# esp32v4.net
KiCad netlist of a schematic drawn in Altium Designer
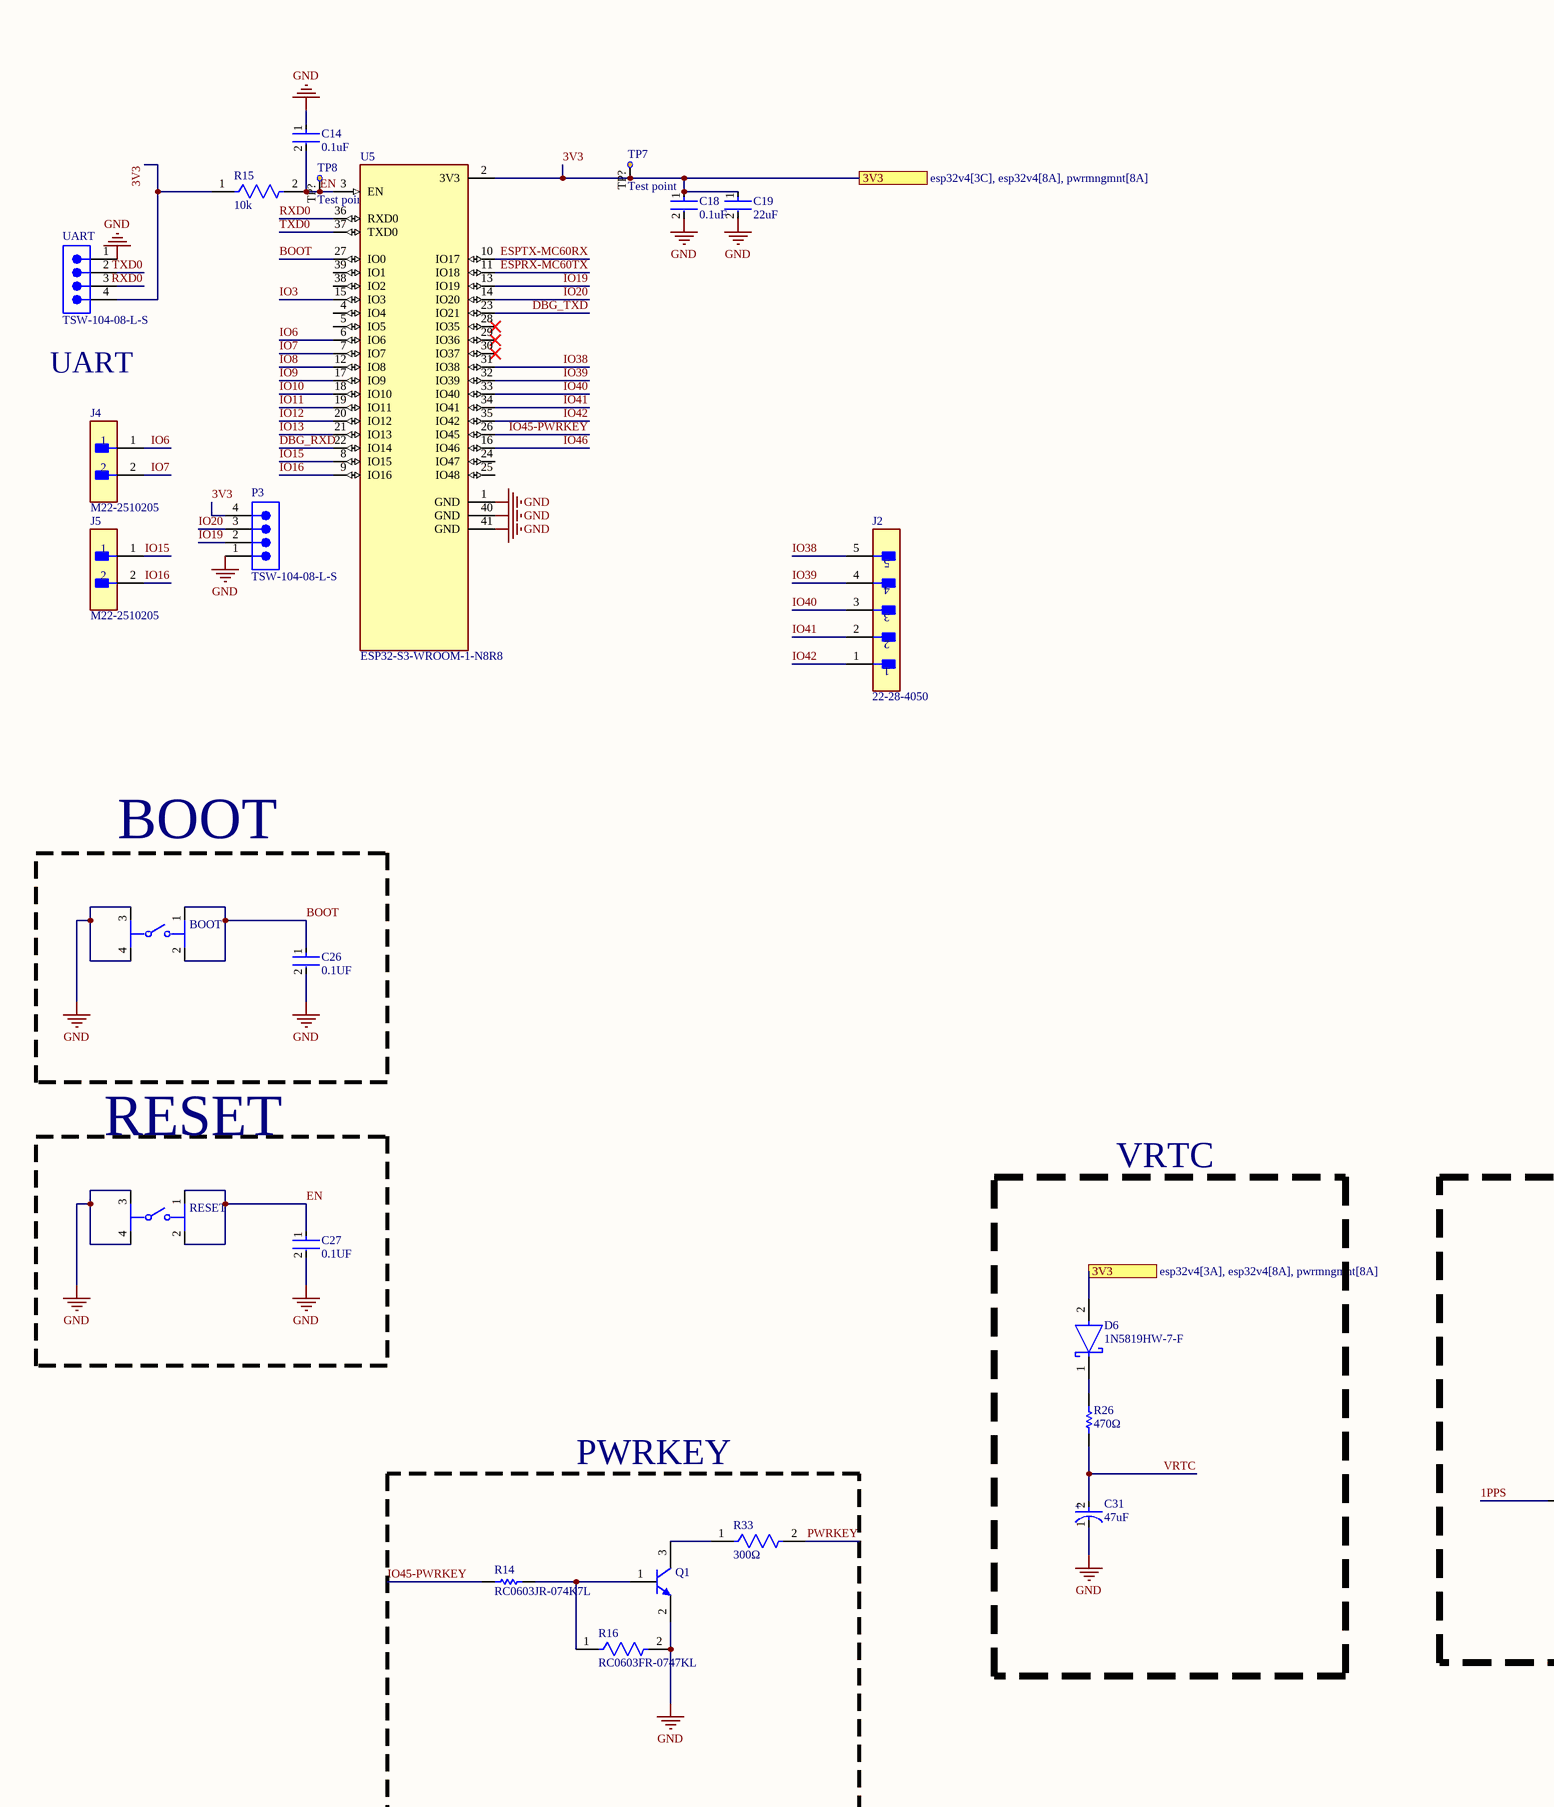
[diagram p0: esp32v4.SchDoc, left]
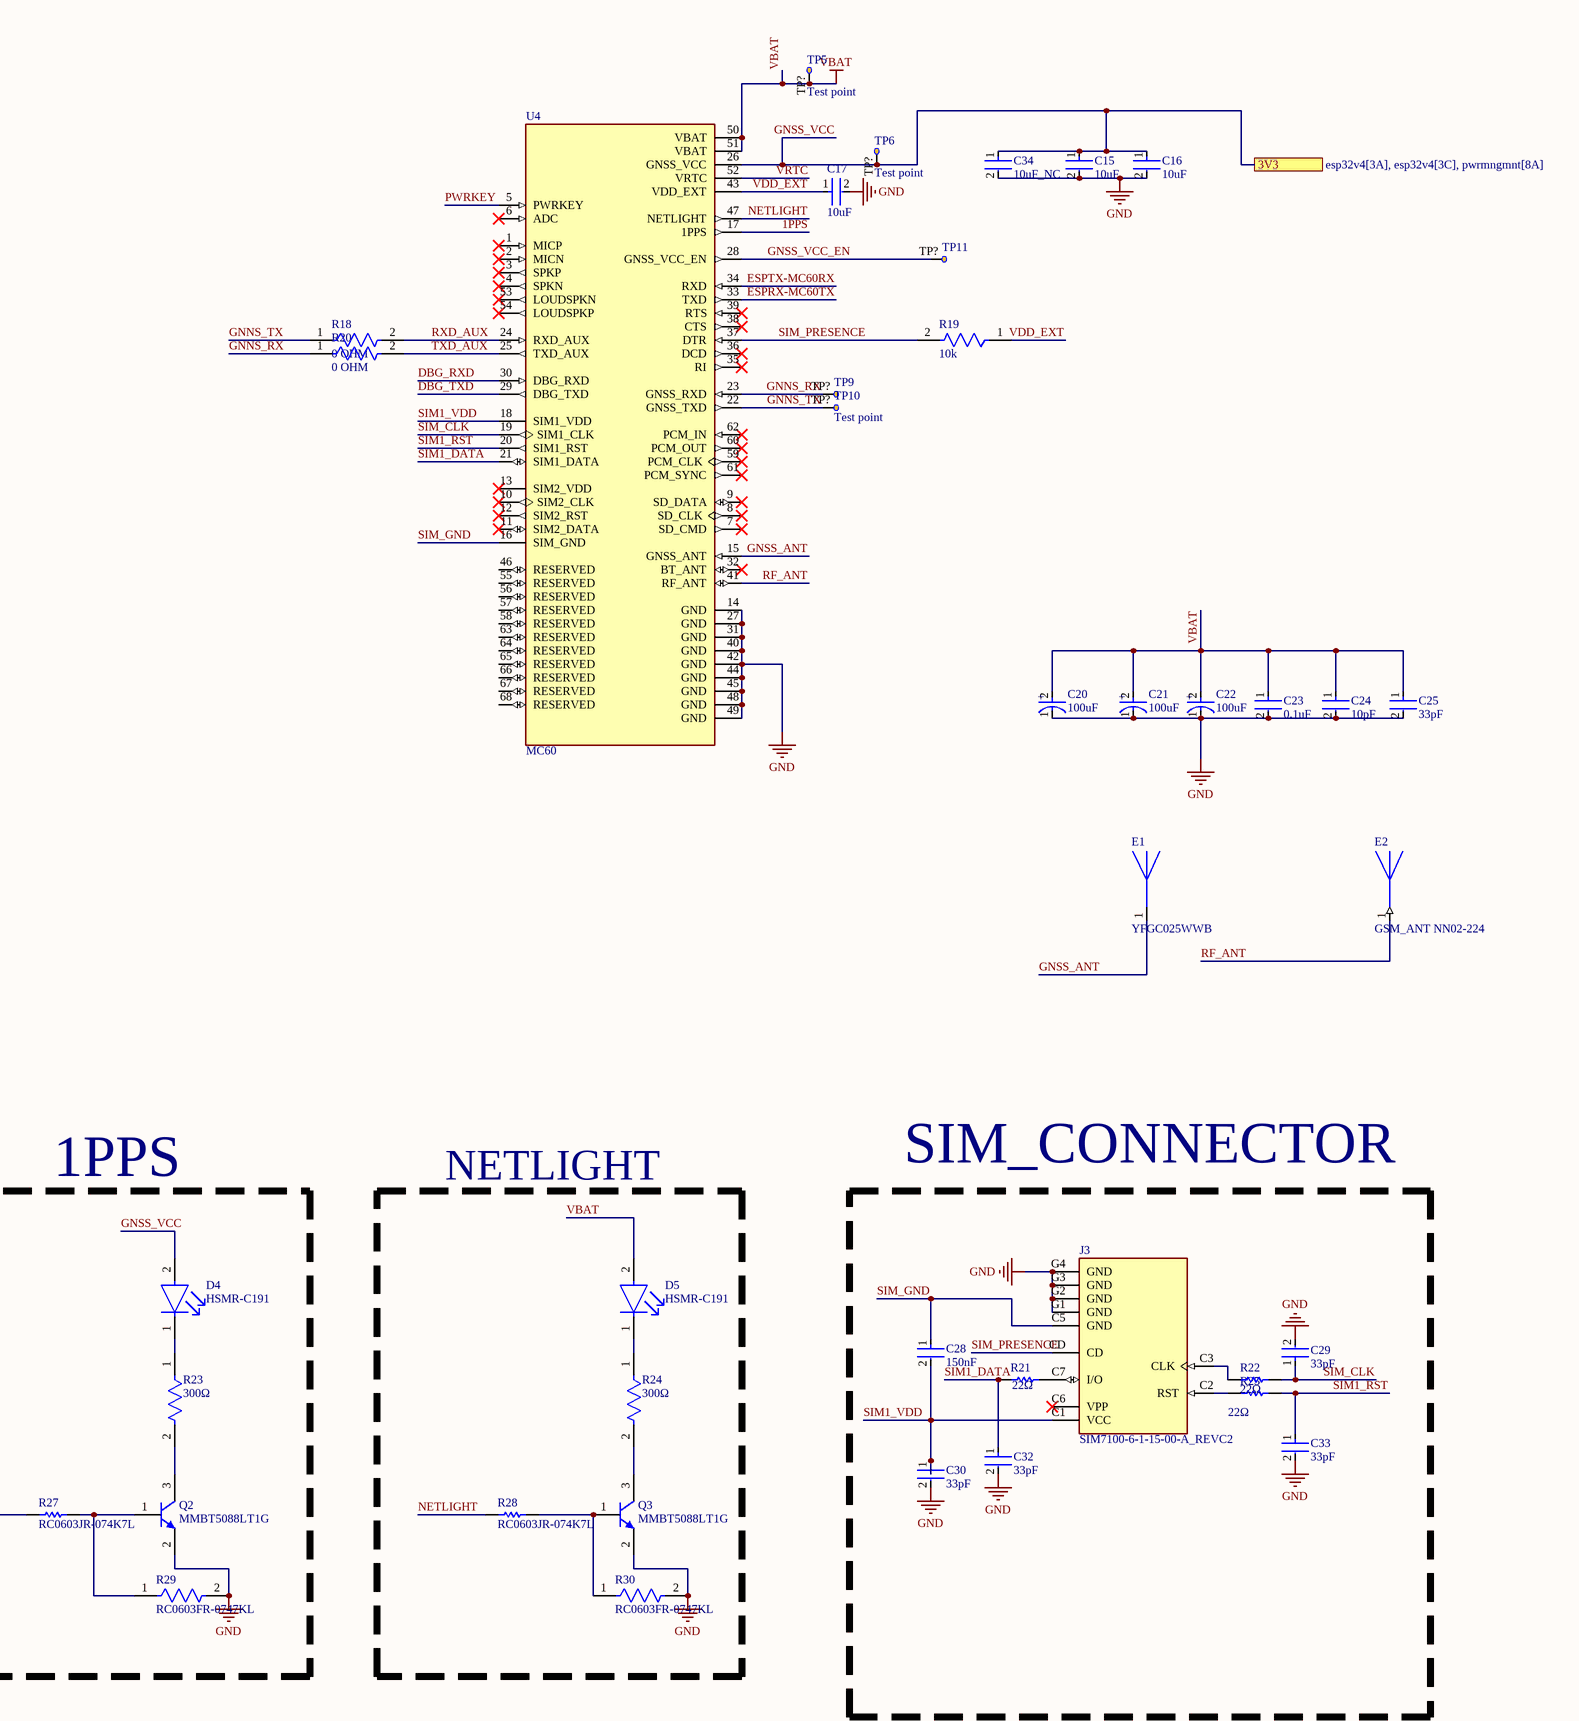
[diagram p1: esp32v4.SchDoc, right]

(export (version "E")
  (design (tool "Eeschema 10.0.6"))
  (components
    (comp (ref "BOOT")
      (value "PTS810SJM250SMTRLFS")
      (footprint "FP-PTS810SJM250SMTRLFS-MFG")
      (description "SWITCH TACTILE SPST-NO 0.05A 16V")
      (libsource (lib "Altium Content Vault") (part "1adf0dd01260c80cf25a44bfd6b99ba"))
    )
    (comp (ref "C14")
      (value "0.1uF")
      (footprint "FP-CC0805-0_85-MFG")
      (description "CAP CER 0.1UF 50V X7R 0805")
      (fields (field (name "TOLERANCE") "0.1") (field (name "MANUFACTURER PART NUMBER") "CC0805KRX7R9BB104"))
      (libsource (lib "Altium Content Vault") (part "11868f565c42a9108669ba33697ecf6"))
    )
    (comp (ref "C15")
      (value "10uF")
      (footprint "FP-C0805C106K4PACTU-MFG")
      (description "CAP CER 10UF 16V X5R 0805")
      (fields (field (name "TOLERANCE") "10%") (field (name "VOLTAGE") "16V"))
      (libsource (lib "Altium Content Vault") (part "e9c51b7dd13d4faca003ae77663ab08"))
    )
    (comp (ref "C16")
      (value "10uF")
      (footprint "FP-CC0805-0_85-MFG")
      (description "CAP CER 0.1UF 25V X7R 0805")
      (fields (field (name "MANUFACTURER PART NUMBER") "CC0805KRX7R8BB104") (field (name "TOLERANCE") "0.1"))
      (libsource (lib "Altium Content Vault") (part "11868f565c42a9108669ba33697ecf6"))
    )
    (comp (ref "C17")
      (value "10uF")
      (footprint "FP-C0805C106K4PACTU-MFG")
      (description "CAP CER 10UF 16V X5R 0805")
      (fields (field (name "TOLERANCE") "10%") (field (name "VOLTAGE") "16V"))
      (libsource (lib "Altium Content Vault") (part "e9c51b7dd13d4faca003ae77663ab08"))
    )
    (comp (ref "C18")
      (value "0.1uF")
      (footprint "FP-CC0805-0_85-MFG")
      (description "CAP CER 0.1UF 25V X7R 0805")
      (fields (field (name "MANUFACTURER PART NUMBER") "CC0805KRX7R8BB104") (field (name "TOLERANCE") "0.1"))
      (libsource (lib "Altium Content Vault") (part "11868f565c42a9108669ba33697ecf6"))
    )
    (comp (ref "C19")
      (value "22uF")
      (footprint "FP-GRM21B-0_15-MFG")
      (description "Chip Multilayer Ceramic Capacitors for General Purpose, 0805, 22uF, X5R, 15%, 20%, 6.3V")
      (fields (field (name "VOLTAGE") "6.3V") (field (name "TOLERANCE") "20%"))
      (libsource (lib "Altium Content Vault") (part "b4654b650e69147ec39a6b967a45e02"))
    )
    (comp (ref "C20")
      (value "100uF")
      (footprint "FP-SC-MFG")
      (description "CAP ALUM 100UF 20% 10V SMD")
      (fields (field (name "TOLERANCE") "20%"))
      (libsource (lib "Altium Content Vault") (part "a00bbbee19879c290e62620ae7e47b1"))
    )
    (comp (ref "C21")
      (value "100uF")
      (footprint "FP-SC-MFG")
      (description "CAP ALUM 100UF 20% 10V SMD")
      (fields (field (name "TOLERANCE") "20%"))
      (libsource (lib "Altium Content Vault") (part "a00bbbee19879c290e62620ae7e47b1"))
    )
    (comp (ref "C22")
      (value "100uF")
      (footprint "FP-SC-MFG")
      (description "CAP ALUM 100UF 20% 10V SMD")
      (fields (field (name "TOLERANCE") "20%"))
      (libsource (lib "Altium Content Vault") (part "a00bbbee19879c290e62620ae7e47b1"))
    )
    (comp (ref "C23")
      (value "0.1uF")
      (footprint "FP-CC0805-0_85-MFG")
      (description "CAP CER 0.1UF 25V X7R 0805")
      (fields (field (name "MANUFACTURER PART NUMBER") "CC0805KRX7R8BB104") (field (name "TOLERANCE") "0.1"))
      (libsource (lib "Altium Content Vault") (part "11868f565c42a9108669ba33697ecf6"))
    )
    (comp (ref "C24")
      (value "10pF")
      (footprint "FP-C0805C-DN-MFG")
      (description "Cap Ceramic 10pF 100V C0G 5% SMD 0805 125C Plastic T/R")
      (fields
        (field (name "MANUFACTURER PART NUMBER") "C0805C100J1GACTU")
        (field (name "OCTOPART") "https://octopart.com/c0805c100j1gactu-kemet-127179")
      )
      (libsource (lib "Altium Content Vault") (part "b4654b650e69147ec39a6b967a45e02"))
    )
    (comp (ref "C25")
      (value "33pF")
      (footprint "FP-C0603C-CF-MFG")
      (description "Capacitor; Ceramic; Cap; 33.0pF; Tol 5%; SMT; Vol-Rtg 50V; C0G; Tape and Reel")
      (fields (field (name "MANUFACTURER PART NUMBER") "C0603C330J5GACTU") (field (name "TOLERANCE") "0.05"))
      (libsource (lib "Altium Content Vault") (part "b4654b650e69147ec39a6b967a45e02"))
    )
    (comp (ref "C26")
      (value "0.1UF")
      (footprint "FP-CC0805-0_85-MFG")
      (description "CAP CER 0.1UF 50V X7R 0805")
      (fields (field (name "TOLERANCE") "0.1") (field (name "MANUFACTURER PART NUMBER") "CC0805KRX7R9BB104"))
      (libsource (lib "Altium Content Vault") (part "11868f565c42a9108669ba33697ecf6"))
    )
    (comp (ref "C27")
      (value "0.1UF")
      (footprint "FP-CC0805-0_85-MFG")
      (description "CAP CER 0.1UF 50V X7R 0805")
      (fields (field (name "TOLERANCE") "0.1") (field (name "MANUFACTURER PART NUMBER") "CC0805KRX7R9BB104"))
      (libsource (lib "Altium Content Vault") (part "11868f565c42a9108669ba33697ecf6"))
    )
    (comp (ref "C28")
      (value "150nF")
      (footprint "FP-CL21-IPC_C")
      (description "CL21 Series 0805 150nF 16V ±10% Tolerance X7R Multilayer Ceramic Chip Capacitor")
      (fields (field (name "TOLERANCE") "10%"))
      (libsource (lib "Altium Content Vault") (part "b4654b650e69147ec39a6b967a45e02"))
    )
    (comp (ref "C29")
      (value "33pF")
      (footprint "FP-0603-L_1_6_0_15-W_0_81-IPC_C")
      (description "General Purpose Ceramic Capacitor, 0603, 33pF, 5%, NP0, 30ppm/°C, 50V")
      (fields (field (name "TOLERANCE") "5%") (field (name "VOLTAGE") "50V"))
      (libsource (lib "Altium Content Vault") (part "02cd4be3c70576c341d710602a673aa"))
    )
    (comp (ref "C30")
      (value "33pF")
      (footprint "FP-0603-L_1_6_0_15-W_0_81-IPC_C")
      (description "General Purpose Ceramic Capacitor, 0603, 33pF, 5%, NP0, 30ppm/°C, 50V")
      (fields (field (name "TOLERANCE") "5%") (field (name "VOLTAGE") "50V"))
      (libsource (lib "Altium Content Vault") (part "02cd4be3c70576c341d710602a673aa"))
    )
    (comp (ref "C31")
      (value "47uF")
      (footprint "FP-OS-CON-SMT-C6-MFG")
      (description "Conductive Polymer Aluminum Solid Capacitors (OS-CON) 47uF ±20% 10V")
      (fields (field (name "TOLERANCE") "20%") (field (name "VOLTAGE") "10V"))
      (libsource (lib "Altium Content Vault") (part "a00bbbee19879c290e62620ae7e47b1"))
    )
    (comp (ref "C32")
      (value "33pF")
      (footprint "FP-0603-L_1_6_0_15-W_0_81-IPC_C")
      (description "General Purpose Ceramic Capacitor, 0603, 33pF, 5%, NP0, 30ppm/°C, 50V")
      (fields (field (name "TOLERANCE") "5%") (field (name "VOLTAGE") "50V"))
      (libsource (lib "Altium Content Vault") (part "02cd4be3c70576c341d710602a673aa"))
    )
    (comp (ref "C33")
      (value "33pF")
      (footprint "FP-0603-L_1_6_0_15-W_0_81-IPC_C")
      (description "General Purpose Ceramic Capacitor, 0603, 33pF, 5%, NP0, 30ppm/°C, 50V")
      (fields (field (name "TOLERANCE") "5%") (field (name "VOLTAGE") "50V"))
      (libsource (lib "Altium Content Vault") (part "02cd4be3c70576c341d710602a673aa"))
    )
    (comp (ref "C34")
      (value "10uF_NC")
      (footprint "FP-C0805C106K4PACTU-MFG")
      (description "CAP CER 10UF 16V X5R 0805")
      (fields (field (name "TOLERANCE") "10%") (field (name "VOLTAGE") "16V"))
      (libsource (lib "Altium Content Vault") (part "e9c51b7dd13d4faca003ae77663ab08"))
    )
    (comp (ref "D4")
      (value "HSMR-C191")
      (footprint "FP-HSMR-C191-MFG")
      (description "HSMR-C191 High-Performance Chip LED Single Color LED, Blue, Untinted Diffused, 1mm")
      (libsource (lib "Altium Content Vault") (part "8706943c75ba83719d021d2fdc84c58"))
    )
    (comp (ref "D5")
      (value "HSMR-C191")
      (footprint "FP-HSMR-C191-MFG")
      (description "HSMR-C191 High-Performance Chip LED Single Color LED, Blue, Untinted Diffused, 1mm")
      (libsource (lib "Altium Content Vault") (part "8706943c75ba83719d021d2fdc84c58"))
    )
    (comp (ref "D6")
      (value "1N5819HW-7-F")
      (footprint "FP-SOD123-IPC_A")
      (description "DIODE SCHOTTKY 40V 1A SOD123")
      (libsource (lib "Altium Content Vault") (part "1d6ec82d83fb6aee721767c19dac4b9"))
    )
    (comp (ref "E1")
      (value "YFGC025WWB")
      (footprint "XDCR_YFGC025WWB")
      (libsource (lib "YFGC025WWB") (part "YFGC025WWB"))
    )
    (comp (ref "E2")
      (value "GSM_ANT NN02-224")
      (footprint "XCVR_NN02-224")
      (fields (field (name "MF") "Ignion") (field (name "MP") "NN02-224"))
      (libsource (lib "NN02-224") (part "NN02-224"))
    )
    (comp (ref "J2")
      (value "22-28-4050")
      (footprint "FP-22-28-4050-MFG")
      (libsource (lib "Altium Content Vault") (part "bf93c07fd2649a848d0ec8585582aab"))
    )
    (comp (ref "J3")
      (value "SIM7100-6-1-15-00-A_REVC2")
      (footprint "GCT_SIM7100-6-1-15-00-A_REVC2")
      (description "7 (6 + 1) Position Card Connector Micro SIM Surface Mount, Right Angle Gold")
      (fields (field (name "MF") "Global Connector Technology") (field (name "MP") "SIM7100-6-1-15-00-A"))
      (libsource (lib "SIM7100-6-1-15-00-A_REVC2") (part "SIM7100-6-1-15-00-A_REVC2"))
    )
    (comp (ref "J4")
      (value "M22-2510205")
      (footprint "FP-M22-2510205-MFG")
      (description "CONN HEADER VERT 2POS 2MM")
      (fields
        (field (name "MANUFACTURER") "Harwin")
        (field (name "OCTOPART") "https://octopart.com/m22-2510205-harwin-2538221")
      )
      (libsource (lib "Altium Content Vault") (part "3bc925449376181038e59eaffc5286c"))
    )
    (comp (ref "J5")
      (value "M22-2510205")
      (footprint "FP-M22-2510205-MFG")
      (description "CONN HEADER VERT 2POS 2MM")
      (fields
        (field (name "MANUFACTURER") "Harwin")
        (field (name "OCTOPART") "https://octopart.com/m22-2510205-harwin-2538221")
      )
      (libsource (lib "Altium Content Vault") (part "3bc925449376181038e59eaffc5286c"))
    )
    (comp (ref "P3")
      (value "TSW-104-08-L-S")
      (footprint "SMTC-TSW-104-08-X-S")
      (description "0.025\" SQ Post Header, Through-hole, Vertical, -55 to 125 degC, 2.54 mm Pitch, 4-Pin, Male, RoHS")
      (fields (field (name "MANUFACTURER") "Samtec"))
      (libsource (lib "Altium Content Vault") (part "SMTC-TSW-104-08-X-S"))
    )
    (comp (ref "Q1")
      (value "MMBT5088LT1G")
      (footprint "ONSC-SOT-23-3-318-08_V")
      (description "Low Noise Transistor, NPN Silicon, 3-Pin SOT-23, Pb-Free, Tape and Reel")
      (fields (field (name "MANUFACTURER") "On Semiconductor"))
      (libsource (lib "Altium Content Vault") (part "ONSC-NPN-B1E2C3-3"))
    )
    (comp (ref "Q2")
      (value "MMBT5088LT1G")
      (footprint "ONSC-SOT-23-3-318-08_V")
      (description "Low Noise Transistor, NPN Silicon, 3-Pin SOT-23, Pb-Free, Tape and Reel")
      (fields (field (name "MANUFACTURER") "On Semiconductor"))
      (libsource (lib "Altium Content Vault") (part "ONSC-NPN-B1E2C3-3"))
    )
    (comp (ref "Q3")
      (value "MMBT5088LT1G")
      (footprint "ONSC-SOT-23-3-318-08_V")
      (description "Low Noise Transistor, NPN Silicon, 3-Pin SOT-23, Pb-Free, Tape and Reel")
      (fields (field (name "MANUFACTURER") "On Semiconductor"))
      (libsource (lib "Altium Content Vault") (part "ONSC-NPN-B1E2C3-3"))
    )
    (comp (ref "R14")
      (value "RC0603JR-074K7L")
      (footprint "RESC1608X55X25ML10T15")
      (description "Chip Resistor, 4.7 KOhm, +/- 5%, 100 mW, -55 to 155 degC, 0603 (1608 Metric), RoHS, Tape and Reel")
      (fields (field (name "TOLERANCE") "5%") (field (name "MANUFACTURER") "Yageo"))
      (libsource (lib "Altium Content Vault") (part "RES-2"))
    )
    (comp (ref "R15")
      (value "10k")
      (footprint "FP-RT0805-MFG")
      (description "RES SMD 10K OHM 0.1% 1/8W 0805")
      (fields
        (field (name "OCTOPART") "https://octopart.com/rt0805brd0710kl-yageo-1290190")
        (field (name "TOLERANCE") "0.0025")
      )
      (libsource (lib "Altium Content Vault") (part "1029c3af85768c4190bb7ad29bc67b5"))
    )
    (comp (ref "R16")
      (value "RC0603FR-0747KL")
      (footprint "FP-RC0603FR-0747KL-MFG")
      (description "RES SMD 47K OHM 1% 1/10W 0603")
      (fields (field (name "TOLERANCE") "1%"))
      (libsource (lib "Altium Content Vault") (part "1029c3af85768c4190bb7ad29bc67b5"))
    )
    (comp (ref "R18")
      (value "0 OHM")
      (footprint "FP-RMCF0805-MFG")
      (description "RES 0 OHM JUMPER 1/8W 0805")
      (libsource (lib "Altium Content Vault") (part "1029c3af85768c4190bb7ad29bc67b5"))
    )
    (comp (ref "R19")
      (value "10k")
      (footprint "FP-RT0603-MFG")
      (description "RES SMD 10K OHM 1% 1/10W 0603")
      (fields
        (field (name "MANUFACTURER") "Yageo")
        (field (name "OCTOPART") "https://octopart.com/rt0603fre0710kl-yageo-40009243")
      )
      (libsource (lib "Altium Content Vault") (part "1029c3af85768c4190bb7ad29bc67b5"))
    )
    (comp (ref "R20")
      (value "0 OHM")
      (footprint "FP-RMCF0805-MFG")
      (description "RES 0 OHM JUMPER 1/8W 0805")
      (libsource (lib "Altium Content Vault") (part "1029c3af85768c4190bb7ad29bc67b5"))
    )
    (comp (ref "R21")
      (value "22Ω")
      (footprint "RESC1005X40X25ML05T05")
      (description "Chip Resistor, 22 Ohm, +/- 1%, 0.1 W, -55 to 155 degC, 0402 (1005 Metric), RoHS, Tape and Reel")
      (fields (field (name "PARTNUMBER") "ERJ-2RKF22R0X") (field (name "TOLERANCE") "1%"))
      (libsource (lib "Altium Content Vault") (part "RES-2"))
    )
    (comp (ref "R22")
      (value "22Ω")
      (footprint "RESC1005X40X25ML05T05")
      (description "Chip Resistor, 22 Ohm, +/- 1%, 0.1 W, -55 to 155 degC, 0402 (1005 Metric), RoHS, Tape and Reel")
      (fields (field (name "PARTNUMBER") "ERJ-2RKF22R0X") (field (name "TOLERANCE") "1%"))
      (libsource (lib "Altium Content Vault") (part "RES-2"))
    )
    (comp (ref "R23")
      (value "300Ω")
      (footprint "FP-CRCW0603-e3-IPC_A")
      (description "RES Thick Film, 300Ω, 1%, 0.1W, 100ppm/°C, 0603")
      (fields (field (name "TOLERANCE") "1%"))
      (libsource (lib "Altium Content Vault") (part "1029c3af85768c4190bb7ad29bc67b5"))
    )
    (comp (ref "R24")
      (value "300Ω")
      (footprint "FP-CRCW0603-e3-IPC_A")
      (description "RES Thick Film, 300Ω, 1%, 0.1W, 100ppm/°C, 0603")
      (fields (field (name "TOLERANCE") "1%"))
      (libsource (lib "Altium Content Vault") (part "1029c3af85768c4190bb7ad29bc67b5"))
    )
    (comp (ref "R25")
      (value "22Ω")
      (footprint "RESC1005X40X25ML05T05")
      (description "Chip Resistor, 22 Ohm, +/- 1%, 0.1 W, -55 to 155 degC, 0402 (1005 Metric), RoHS, Tape and Reel")
      (fields (field (name "PARTNUMBER") "ERJ-2RKF22R0X") (field (name "TOLERANCE") "1%"))
      (libsource (lib "Altium Content Vault") (part "RES-2"))
    )
    (comp (ref "R26")
      (value "470Ω")
      (footprint "RESC3216X60X45ML10T20")
      (fields (field (name "MANUFACTURER") "Vishay Dale") (field (name "PART NUMBER") "CRCW1206470RFKEA"))
      (libsource (lib "Altium Content Vault") (part "RES"))
    )
    (comp (ref "R27")
      (value "RC0603JR-074K7L")
      (footprint "RESC1608X55X25ML10T15")
      (description "Chip Resistor, 4.7 KOhm, +/- 5%, 100 mW, -55 to 155 degC, 0603 (1608 Metric), RoHS, Tape and Reel")
      (fields (field (name "TOLERANCE") "5%") (field (name "MANUFACTURER") "Yageo"))
      (libsource (lib "Altium Content Vault") (part "RES-2"))
    )
    (comp (ref "R28")
      (value "RC0603JR-074K7L")
      (footprint "RESC1608X55X25ML10T15")
      (description "Chip Resistor, 4.7 KOhm, +/- 5%, 100 mW, -55 to 155 degC, 0603 (1608 Metric), RoHS, Tape and Reel")
      (fields (field (name "TOLERANCE") "5%") (field (name "MANUFACTURER") "Yageo"))
      (libsource (lib "Altium Content Vault") (part "RES-2"))
    )
    (comp (ref "R29")
      (value "RC0603FR-0747KL")
      (footprint "FP-RC0603FR-0747KL-MFG")
      (description "RES SMD 47K OHM 1% 1/10W 0603")
      (fields (field (name "TOLERANCE") "1%"))
      (libsource (lib "Altium Content Vault") (part "1029c3af85768c4190bb7ad29bc67b5"))
    )
    (comp (ref "R30")
      (value "RC0603FR-0747KL")
      (footprint "FP-RC0603FR-0747KL-MFG")
      (description "RES SMD 47K OHM 1% 1/10W 0603")
      (fields (field (name "TOLERANCE") "1%"))
      (libsource (lib "Altium Content Vault") (part "1029c3af85768c4190bb7ad29bc67b5"))
    )
    (comp (ref "R33")
      (value "300Ω")
      (footprint "FP-CRCW0603-e3-IPC_A")
      (description "RES Thick Film, 300Ω, 1%, 0.1W, 100ppm/°C, 0603")
      (fields (field (name "TOLERANCE") "1%"))
      (libsource (lib "Altium Content Vault") (part "1029c3af85768c4190bb7ad29bc67b5"))
    )
    (comp (ref "RESET")
      (value "PTS810SJM250SMTRLFS")
      (footprint "FP-PTS810SJM250SMTRLFS-MFG")
      (description "SWITCH TACTILE SPST-NO 0.05A 16V")
      (libsource (lib "Altium Content Vault") (part "1adf0dd01260c80cf25a44bfd6b99ba"))
    )
    (comp (ref "TP5")
      (value "Test point")
      (footprint "Test_Point")
      (libsource (lib "Test_Point") (part "Test_Point"))
    )
    (comp (ref "TP6")
      (value "Test point")
      (footprint "Test_Point")
      (libsource (lib "Test_Point") (part "Test_Point"))
    )
    (comp (ref "TP7")
      (value "Test point")
      (footprint "Test_Point")
      (libsource (lib "Test_Point") (part "Test_Point"))
    )
    (comp (ref "TP8")
      (value "Test point")
      (footprint "Test_Point")
      (libsource (lib "Test_Point") (part "Test_Point"))
    )
    (comp (ref "TP9")
      (value "Test point")
      (footprint "Test_Point")
      (libsource (lib "Test_Point") (part "Test_Point"))
    )
    (comp (ref "TP10")
      (value "Test point")
      (footprint "Test_Point")
      (libsource (lib "Test_Point") (part "Test_Point"))
    )
    (comp (ref "TP11")
      (value "Test point")
      (footprint "Test_Point")
      (libsource (lib "Test_Point") (part "Test_Point"))
    )
    (comp (ref "U4")
      (value "MC60")
      (footprint "XCVR_MC60")
      (fields (field (name "MF") "Quectel"))
      (libsource (lib "MC60") (part "MC60"))
    )
    (comp (ref "U5")
      (value "ESP32-S3-WROOM-1-N8R8")
      (footprint "XCVR_ESP32S3WROOM1N8R8")
      (description "Bluetooth, WiFi 802.11b/g/n, Bluetooth v5.0 Transceiver Module 2.4GHz PCB Trace Surface Mount")
      (fields (field (name "MF") "Espressif Systems"))
      (libsource (lib "esp32") (part "ESP32-S3-WROOM-1-N8R8"))
    )
    (comp (ref "UART")
      (value "TSW-104-08-L-S")
      (footprint "SMTC-TSW-104-08-X-S")
      (description "0.025\" SQ Post Header, Through-hole, Vertical, -55 to 125 degC, 2.54 mm Pitch, 4-Pin, Male, RoHS")
      (fields (field (name "MANUFACTURER") "Samtec"))
      (libsource (lib "Altium Content Vault") (part "SMTC-TSW-104-08-X-S"))
    )
  )
  (nets
    (net (code "1") (name "/1PPS") (class "Default")
      (node (ref "R27") (pin "1") (pinfunction "1_1") (pintype "passive"))
      (node (ref "U4") (pin "17") (pinfunction "1PPS_17") (pintype "output"))
    )
    (net (code "2") (name "/3V3") (class "Default")
      (node (ref "C15") (pin "1") (pinfunction "1_1") (pintype "passive"))
      (node (ref "C16") (pin "1") (pinfunction "1_1") (pintype "passive"))
      (node (ref "C18") (pin "1") (pinfunction "1_1") (pintype "passive"))
      (node (ref "C19") (pin "1") (pinfunction "1_1") (pintype "passive"))
      (node (ref "C34") (pin "1") (pinfunction "1_1") (pintype "passive"))
      (node (ref "D4") (pin "2") (pinfunction "A_2") (pintype "passive"))
      (node (ref "D6") (pin "2") (pinfunction "A_2") (pintype "passive"))
      (node (ref "P3") (pin "4") (pinfunction "4_4") (pintype "passive"))
      (node (ref "R15") (pin "1") (pinfunction "1_1") (pintype "passive"))
      (node (ref "TP6") (pin "TP?") (pinfunction "Test_point_TP?") (pintype "passive"))
      (node (ref "TP7") (pin "TP?") (pinfunction "Test_point_TP?") (pintype "passive"))
      (node (ref "U4") (pin "26") (pinfunction "GNSS_VCC_26") (pintype "power_in"))
      (node (ref "U5") (pin "2") (pinfunction "3V3_2") (pintype "power_in"))
      (node (ref "UART") (pin "4") (pinfunction "4_4") (pintype "passive"))
    )
    (net (code "3") (name "/BOOT") (class "Default")
      (node (ref "BOOT") (pin "1") (pinfunction "1_1") (pintype "passive"))
      (node (ref "BOOT") (pin "2") (pinfunction "2_2") (pintype "passive"))
      (node (ref "C26") (pin "1") (pinfunction "1_1") (pintype "passive"))
      (node (ref "U5") (pin "27") (pinfunction "IO0_27") (pintype "bidirectional"))
    )
    (net (code "4") (name "/DBG_RXD") (class "Default")
      (node (ref "U4") (pin "30") (pinfunction "DBG_RXD_30") (pintype "input"))
      (node (ref "U5") (pin "22") (pinfunction "IO14_22") (pintype "bidirectional"))
    )
    (net (code "5") (name "/DBG_TXD") (class "Default")
      (node (ref "U4") (pin "29") (pinfunction "DBG_TXD_29") (pintype "output"))
      (node (ref "U5") (pin "23") (pinfunction "IO21_23") (pintype "bidirectional"))
    )
    (net (code "6") (name "/EN") (class "Default")
      (node (ref "C14") (pin "2") (pinfunction "2_2") (pintype "passive"))
      (node (ref "C27") (pin "1") (pinfunction "1_1") (pintype "passive"))
      (node (ref "R15") (pin "2") (pinfunction "2_2") (pintype "passive"))
      (node (ref "RESET") (pin "1") (pinfunction "1_1") (pintype "passive"))
      (node (ref "RESET") (pin "2") (pinfunction "2_2") (pintype "passive"))
      (node (ref "TP8") (pin "TP?") (pinfunction "Test_point_TP?") (pintype "passive"))
      (node (ref "U5") (pin "3") (pinfunction "EN_3") (pintype "input"))
    )
    (net (code "7") (name "/ESPRX-MC60TX") (class "Default")
      (node (ref "U4") (pin "33") (pinfunction "TXD_33") (pintype "output"))
      (node (ref "U5") (pin "11") (pinfunction "IO18_11") (pintype "bidirectional"))
    )
    (net (code "8") (name "/ESPTX-MC60RX") (class "Default")
      (node (ref "U4") (pin "34") (pinfunction "RXD_34") (pintype "input"))
      (node (ref "U5") (pin "10") (pinfunction "IO17_10") (pintype "bidirectional"))
    )
    (net (code "9") (name "/GNNS_RX") (class "Default")
      (node (ref "R20") (pin "1") (pinfunction "1_1") (pintype "passive"))
      (node (ref "TP9") (pin "TP?") (pinfunction "Test_point_TP?") (pintype "passive"))
      (node (ref "U4") (pin "23") (pinfunction "GNSS_RXD_23") (pintype "input"))
    )
    (net (code "10") (name "/GNNS_TX") (class "Default")
      (node (ref "R18") (pin "1") (pinfunction "1_1") (pintype "passive"))
      (node (ref "TP10") (pin "TP?") (pinfunction "Test_point_TP?") (pintype "passive"))
      (node (ref "U4") (pin "22") (pinfunction "GNSS_TXD_22") (pintype "output"))
    )
    (net (code "11") (name "/GNSS_ANT") (class "Default")
      (node (ref "E1") (pin "1") (pinfunction "FEED_1") (pintype "passive"))
      (node (ref "U4") (pin "15") (pinfunction "GNSS_ANT_15") (pintype "input"))
    )
    (net (code "12") (name "/GNSS_VCC_EN") (class "Default")
      (node (ref "TP11") (pin "TP?") (pinfunction "Test_point_TP?") (pintype "passive"))
      (node (ref "U4") (pin "28") (pinfunction "GNSS_VCC_EN_28") (pintype "output"))
    )
    (net (code "13") (name "/IO3") (class "Default")
      (node (ref "U5") (pin "15") (pinfunction "IO3_15") (pintype "bidirectional"))
    )
    (net (code "14") (name "/IO6") (class "Default")
      (node (ref "J4") (pin "1") (pinfunction "1_1") (pintype "passive"))
      (node (ref "U5") (pin "6") (pinfunction "IO6_6") (pintype "bidirectional"))
    )
    (net (code "15") (name "/IO7") (class "Default")
      (node (ref "J4") (pin "2") (pinfunction "2_2") (pintype "passive"))
      (node (ref "U5") (pin "7") (pinfunction "IO7_7") (pintype "bidirectional"))
    )
    (net (code "16") (name "/IO8") (class "Default")
      (node (ref "U5") (pin "12") (pinfunction "IO8_12") (pintype "bidirectional"))
    )
    (net (code "17") (name "/IO9") (class "Default")
      (node (ref "U5") (pin "17") (pinfunction "IO9_17") (pintype "bidirectional"))
    )
    (net (code "18") (name "/IO10") (class "Default")
      (node (ref "U5") (pin "18") (pinfunction "IO10_18") (pintype "bidirectional"))
    )
    (net (code "19") (name "/IO11") (class "Default")
      (node (ref "U5") (pin "19") (pinfunction "IO11_19") (pintype "bidirectional"))
    )
    (net (code "20") (name "/IO12") (class "Default")
      (node (ref "U5") (pin "20") (pinfunction "IO12_20") (pintype "bidirectional"))
    )
    (net (code "21") (name "/IO13") (class "Default")
      (node (ref "U5") (pin "21") (pinfunction "IO13_21") (pintype "bidirectional"))
    )
    (net (code "22") (name "/IO15") (class "Default")
      (node (ref "J5") (pin "1") (pinfunction "1_1") (pintype "passive"))
      (node (ref "U5") (pin "8") (pinfunction "IO15_8") (pintype "bidirectional"))
    )
    (net (code "23") (name "/IO16") (class "Default")
      (node (ref "J5") (pin "2") (pinfunction "2_2") (pintype "passive"))
      (node (ref "U5") (pin "9") (pinfunction "IO16_9") (pintype "bidirectional"))
    )
    (net (code "24") (name "/IO19") (class "Default")
      (node (ref "P3") (pin "2") (pinfunction "2_2") (pintype "passive"))
      (node (ref "U5") (pin "13") (pinfunction "IO19_13") (pintype "bidirectional"))
    )
    (net (code "25") (name "/IO20") (class "Default")
      (node (ref "P3") (pin "3") (pinfunction "3_3") (pintype "passive"))
      (node (ref "U5") (pin "14") (pinfunction "IO20_14") (pintype "bidirectional"))
    )
    (net (code "26") (name "/IO38") (class "Default")
      (node (ref "J2") (pin "5") (pinfunction "5_5") (pintype "passive"))
      (node (ref "U5") (pin "31") (pinfunction "IO38_31") (pintype "bidirectional"))
    )
    (net (code "27") (name "/IO39") (class "Default")
      (node (ref "J2") (pin "4") (pinfunction "4_4") (pintype "passive"))
      (node (ref "U5") (pin "32") (pinfunction "IO39_32") (pintype "bidirectional"))
    )
    (net (code "28") (name "/IO40") (class "Default")
      (node (ref "J2") (pin "3") (pinfunction "3_3") (pintype "passive"))
      (node (ref "U5") (pin "33") (pinfunction "IO40_33") (pintype "bidirectional"))
    )
    (net (code "29") (name "/IO41") (class "Default")
      (node (ref "J2") (pin "2") (pinfunction "2_2") (pintype "passive"))
      (node (ref "U5") (pin "34") (pinfunction "IO41_34") (pintype "bidirectional"))
    )
    (net (code "30") (name "/IO42") (class "Default")
      (node (ref "J2") (pin "1") (pinfunction "1_1") (pintype "passive"))
      (node (ref "U5") (pin "35") (pinfunction "IO42_35") (pintype "bidirectional"))
    )
    (net (code "31") (name "/IO45-PWRKEY") (class "Default")
      (node (ref "R14") (pin "1") (pinfunction "1_1") (pintype "passive"))
      (node (ref "U5") (pin "26") (pinfunction "IO45_26") (pintype "bidirectional"))
    )
    (net (code "32") (name "/IO46") (class "Default")
      (node (ref "U5") (pin "16") (pinfunction "IO46_16") (pintype "bidirectional"))
    )
    (net (code "33") (name "/NETLIGHT") (class "Default")
      (node (ref "R28") (pin "1") (pinfunction "1_1") (pintype "passive"))
      (node (ref "U4") (pin "47") (pinfunction "NETLIGHT_47") (pintype "output"))
    )
    (net (code "34") (name "/PWRKEY") (class "Default")
      (node (ref "R33") (pin "2") (pinfunction "2_2") (pintype "passive"))
      (node (ref "U4") (pin "5") (pinfunction "PWRKEY_5") (pintype "input"))
    )
    (net (code "35") (name "/RF_ANT") (class "Default")
      (node (ref "E2") (pin "1") (pinfunction "FEED_1") (pintype "input"))
      (node (ref "U4") (pin "41") (pinfunction "RF_ANT_41") (pintype "bidirectional"))
    )
    (net (code "36") (name "/RXD0") (class "Default")
      (node (ref "U5") (pin "36") (pinfunction "RXD0_36") (pintype "bidirectional"))
      (node (ref "UART") (pin "3") (pinfunction "3_3") (pintype "passive"))
    )
    (net (code "37") (name "/RXD_AUX") (class "Default")
      (node (ref "R18") (pin "2") (pinfunction "2_2") (pintype "passive"))
      (node (ref "U4") (pin "24") (pinfunction "RXD_AUX_24") (pintype "input"))
    )
    (net (code "38") (name "/SIM1_DATA") (class "Default")
      (node (ref "C32") (pin "1") (pinfunction "1_1") (pintype "passive"))
      (node (ref "R21") (pin "1") (pinfunction "1_1") (pintype "passive"))
      (node (ref "U4") (pin "21") (pinfunction "SIM1_DATA_21") (pintype "bidirectional"))
    )
    (net (code "39") (name "/SIM1_RST") (class "Default")
      (node (ref "C33") (pin "1") (pinfunction "1_1") (pintype "passive"))
      (node (ref "R25") (pin "2") (pinfunction "2_2") (pintype "passive"))
      (node (ref "U4") (pin "20") (pinfunction "SIM1_RST_20") (pintype "output"))
    )
    (net (code "40") (name "/SIM1_VDD") (class "Default")
      (node (ref "C28") (pin "2") (pinfunction "2_2") (pintype "passive"))
      (node (ref "C30") (pin "1") (pinfunction "1_1") (pintype "passive"))
      (node (ref "J3") (pin "C1") (pinfunction "VCC_C1") (pintype "power_in"))
      (node (ref "U4") (pin "18") (pinfunction "SIM1_VDD_18") (pintype "power_in"))
    )
    (net (code "41") (name "/SIM_CLK") (class "Default")
      (node (ref "C29") (pin "1") (pinfunction "1_1") (pintype "passive"))
      (node (ref "R22") (pin "2") (pinfunction "2_2") (pintype "passive"))
      (node (ref "U4") (pin "19") (pinfunction "SIM1_CLK_19") (pintype "output"))
    )
    (net (code "42") (name "/SIM_GND") (class "Default")
      (node (ref "C28") (pin "1") (pinfunction "1_1") (pintype "passive"))
      (node (ref "J3") (pin "C5") (pinfunction "GND_C5") (pintype "power_in"))
      (node (ref "U4") (pin "16") (pinfunction "SIM_GND_16") (pintype "power_in"))
    )
    (net (code "43") (name "/SIM_PRESENCE") (class "Default")
      (node (ref "J3") (pin "CD") (pinfunction "CD_CD") (pintype "passive"))
      (node (ref "R19") (pin "2") (pinfunction "2_2") (pintype "passive"))
      (node (ref "U4") (pin "37") (pinfunction "DTR_37") (pintype "input"))
    )
    (net (code "44") (name "/TXD0") (class "Default")
      (node (ref "U5") (pin "37") (pinfunction "TXD0_37") (pintype "bidirectional"))
      (node (ref "UART") (pin "2") (pinfunction "2_2") (pintype "passive"))
    )
    (net (code "45") (name "/TXD_AUX") (class "Default")
      (node (ref "R20") (pin "2") (pinfunction "2_2") (pintype "passive"))
      (node (ref "U4") (pin "25") (pinfunction "TXD_AUX_25") (pintype "output"))
    )
    (net (code "46") (name "/VDD_EXT") (class "Default")
      (node (ref "C17") (pin "1") (pinfunction "1_1") (pintype "passive"))
      (node (ref "R19") (pin "1") (pinfunction "1_1") (pintype "passive"))
      (node (ref "U4") (pin "43") (pinfunction "VDD_EXT_43") (pintype "power_in"))
    )
    (net (code "47") (name "/VRTC") (class "Default")
      (node (ref "C31") (pin "2") (pinfunction "A_2") (pintype "passive"))
      (node (ref "R26") (pin "2") (pinfunction "2_2") (pintype "passive"))
      (node (ref "U4") (pin "52") (pinfunction "VRTC_52") (pintype "power_in"))
    )
    (net (code "48") (name "GND") (class "Default")
      (node (ref "BOOT") (pin "3") (pinfunction "3_3") (pintype "passive"))
      (node (ref "BOOT") (pin "4") (pinfunction "4_4") (pintype "passive"))
      (node (ref "C14") (pin "1") (pinfunction "1_1") (pintype "passive"))
      (node (ref "C15") (pin "2") (pinfunction "2_2") (pintype "passive"))
      (node (ref "C16") (pin "2") (pinfunction "2_2") (pintype "passive"))
      (node (ref "C17") (pin "2") (pinfunction "2_2") (pintype "passive"))
      (node (ref "C18") (pin "2") (pinfunction "2_2") (pintype "passive"))
      (node (ref "C19") (pin "2") (pinfunction "2_2") (pintype "passive"))
      (node (ref "C20") (pin "1") (pinfunction "C_1") (pintype "passive"))
      (node (ref "C21") (pin "1") (pinfunction "C_1") (pintype "passive"))
      (node (ref "C22") (pin "1") (pinfunction "C_1") (pintype "passive"))
      (node (ref "C23") (pin "2") (pinfunction "2_2") (pintype "passive"))
      (node (ref "C24") (pin "2") (pinfunction "2_2") (pintype "passive"))
      (node (ref "C25") (pin "2") (pinfunction "2_2") (pintype "passive"))
      (node (ref "C26") (pin "2") (pinfunction "2_2") (pintype "passive"))
      (node (ref "C27") (pin "2") (pinfunction "2_2") (pintype "passive"))
      (node (ref "C29") (pin "2") (pinfunction "2_2") (pintype "passive"))
      (node (ref "C30") (pin "2") (pinfunction "2_2") (pintype "passive"))
      (node (ref "C31") (pin "1") (pinfunction "C_1") (pintype "passive"))
      (node (ref "C32") (pin "2") (pinfunction "2_2") (pintype "passive"))
      (node (ref "C33") (pin "2") (pinfunction "2_2") (pintype "passive"))
      (node (ref "C34") (pin "2") (pinfunction "2_2") (pintype "passive"))
      (node (ref "J3") (pin "G1") (pinfunction "GND_G1") (pintype "power_in"))
      (node (ref "J3") (pin "G2") (pinfunction "GND_G2") (pintype "power_in"))
      (node (ref "J3") (pin "G3") (pinfunction "GND_G3") (pintype "power_in"))
      (node (ref "J3") (pin "G4") (pinfunction "GND_G4") (pintype "power_in"))
      (node (ref "P3") (pin "1") (pinfunction "1_1") (pintype "passive"))
      (node (ref "Q1") (pin "2") (pinfunction "E_2") (pintype "passive"))
      (node (ref "Q2") (pin "2") (pinfunction "E_2") (pintype "passive"))
      (node (ref "Q3") (pin "2") (pinfunction "E_2") (pintype "passive"))
      (node (ref "R16") (pin "2") (pinfunction "2_2") (pintype "passive"))
      (node (ref "R29") (pin "2") (pinfunction "2_2") (pintype "passive"))
      (node (ref "R30") (pin "2") (pinfunction "2_2") (pintype "passive"))
      (node (ref "RESET") (pin "3") (pinfunction "3_3") (pintype "passive"))
      (node (ref "RESET") (pin "4") (pinfunction "4_4") (pintype "passive"))
      (node (ref "U4") (pin "14") (pinfunction "GND_14") (pintype "power_in"))
      (node (ref "U4") (pin "27") (pinfunction "GND_27") (pintype "power_in"))
      (node (ref "U4") (pin "31") (pinfunction "GND_31") (pintype "power_in"))
      (node (ref "U4") (pin "40") (pinfunction "GND_40") (pintype "power_in"))
      (node (ref "U4") (pin "42") (pinfunction "GND_42") (pintype "power_in"))
      (node (ref "U4") (pin "44") (pinfunction "GND_44") (pintype "power_in"))
      (node (ref "U4") (pin "45") (pinfunction "GND_45") (pintype "power_in"))
      (node (ref "U4") (pin "48") (pinfunction "GND_48") (pintype "power_in"))
      (node (ref "U4") (pin "49") (pinfunction "GND_49") (pintype "power_in"))
      (node (ref "U5") (pin "1") (pinfunction "GND_1") (pintype "power_in"))
      (node (ref "U5") (pin "40") (pinfunction "GND_40") (pintype "power_in"))
      (node (ref "U5") (pin "41") (pinfunction "GND_41") (pintype "power_in"))
      (node (ref "UART") (pin "1") (pinfunction "1_1") (pintype "passive"))
    )
    (net (code "49") (name "Net-(D4-C)") (class "Default")
      (node (ref "D4") (pin "1") (pinfunction "C_1") (pintype "passive"))
      (node (ref "R23") (pin "1") (pinfunction "1_1") (pintype "passive"))
    )
    (net (code "50") (name "Net-(D5-C)") (class "Default")
      (node (ref "D5") (pin "1") (pinfunction "C_1") (pintype "passive"))
      (node (ref "R24") (pin "1") (pinfunction "1_1") (pintype "passive"))
    )
    (net (code "51") (name "Net-(D6-C)") (class "Default")
      (node (ref "D6") (pin "1") (pinfunction "C_1") (pintype "passive"))
      (node (ref "R26") (pin "1") (pinfunction "1_1") (pintype "passive"))
    )
    (net (code "52") (name "Net-(J3-CLK)") (class "Default")
      (node (ref "J3") (pin "C3") (pinfunction "CLK_C3") (pintype "input"))
      (node (ref "R22") (pin "1") (pinfunction "1_1") (pintype "passive"))
    )
    (net (code "53") (name "Net-(J3-I{slash}O)") (class "Default")
      (node (ref "J3") (pin "C7") (pinfunction "I/O_C7") (pintype "bidirectional"))
      (node (ref "R21") (pin "2") (pinfunction "2_2") (pintype "passive"))
    )
    (net (code "54") (name "Net-(J3-RST)") (class "Default")
      (node (ref "J3") (pin "C2") (pinfunction "RST_C2") (pintype "input"))
      (node (ref "R25") (pin "1") (pinfunction "1_1") (pintype "passive"))
    )
    (net (code "55") (name "Net-(Q1-B)") (class "Default")
      (node (ref "Q1") (pin "1") (pinfunction "B_1") (pintype "passive"))
      (node (ref "R14") (pin "2") (pinfunction "2_2") (pintype "passive"))
      (node (ref "R16") (pin "1") (pinfunction "1_1") (pintype "passive"))
    )
    (net (code "56") (name "Net-(Q1-C)") (class "Default")
      (node (ref "Q1") (pin "3") (pinfunction "C_3") (pintype "passive"))
      (node (ref "R33") (pin "1") (pinfunction "1_1") (pintype "passive"))
    )
    (net (code "57") (name "Net-(Q2-B)") (class "Default")
      (node (ref "Q2") (pin "1") (pinfunction "B_1") (pintype "passive"))
      (node (ref "R27") (pin "2") (pinfunction "2_2") (pintype "passive"))
      (node (ref "R29") (pin "1") (pinfunction "1_1") (pintype "passive"))
    )
    (net (code "58") (name "Net-(Q2-C)") (class "Default")
      (node (ref "Q2") (pin "3") (pinfunction "C_3") (pintype "passive"))
      (node (ref "R23") (pin "2") (pinfunction "2_2") (pintype "passive"))
    )
    (net (code "59") (name "Net-(Q3-B)") (class "Default")
      (node (ref "Q3") (pin "1") (pinfunction "B_1") (pintype "passive"))
      (node (ref "R28") (pin "2") (pinfunction "2_2") (pintype "passive"))
      (node (ref "R30") (pin "1") (pinfunction "1_1") (pintype "passive"))
    )
    (net (code "60") (name "Net-(Q3-C)") (class "Default")
      (node (ref "Q3") (pin "3") (pinfunction "C_3") (pintype "passive"))
      (node (ref "R24") (pin "2") (pinfunction "2_2") (pintype "passive"))
    )
    (net (code "61") (name "VBAT") (class "Default")
      (node (ref "C20") (pin "2") (pinfunction "A_2") (pintype "passive"))
      (node (ref "C21") (pin "2") (pinfunction "A_2") (pintype "passive"))
      (node (ref "C22") (pin "2") (pinfunction "A_2") (pintype "passive"))
      (node (ref "C23") (pin "1") (pinfunction "1_1") (pintype "passive"))
      (node (ref "C24") (pin "1") (pinfunction "1_1") (pintype "passive"))
      (node (ref "C25") (pin "1") (pinfunction "1_1") (pintype "passive"))
      (node (ref "D5") (pin "2") (pinfunction "A_2") (pintype "passive"))
      (node (ref "TP5") (pin "TP?") (pinfunction "Test_point_TP?") (pintype "passive"))
      (node (ref "U4") (pin "50") (pinfunction "VBAT_50") (pintype "power_in"))
      (node (ref "U4") (pin "51") (pinfunction "VBAT_51") (pintype "power_in"))
    )
    (net (code "62") (name "unconnected-(J3-VPP-PadC6)") (class "Default")
      (node (ref "J3") (pin "C6") (pinfunction "VPP_C6") (pintype "power_in+no_connect"))
    )
    (net (code "63") (name "unconnected-(U4-ADC-Pad6)") (class "Default")
      (node (ref "U4") (pin "6") (pinfunction "ADC_6") (pintype "input+no_connect"))
    )
    (net (code "64") (name "unconnected-(U4-BT_ANT-Pad32)") (class "Default")
      (node (ref "U4") (pin "32") (pinfunction "BT_ANT_32") (pintype "bidirectional+no_connect"))
    )
    (net (code "65") (name "unconnected-(U4-CTS-Pad38)") (class "Default")
      (node (ref "U4") (pin "38") (pinfunction "CTS_38") (pintype "output+no_connect"))
    )
    (net (code "66") (name "unconnected-(U4-DCD-Pad36)") (class "Default")
      (node (ref "U4") (pin "36") (pinfunction "DCD_36") (pintype "output+no_connect"))
    )
    (net (code "67") (name "unconnected-(U4-LOUDSPKN-Pad53)") (class "Default")
      (node (ref "U4") (pin "53") (pinfunction "LOUDSPKN_53") (pintype "output+no_connect"))
    )
    (net (code "68") (name "unconnected-(U4-LOUDSPKP-Pad54)") (class "Default")
      (node (ref "U4") (pin "54") (pinfunction "LOUDSPKP_54") (pintype "output+no_connect"))
    )
    (net (code "69") (name "unconnected-(U4-MICN-Pad2)") (class "Default")
      (node (ref "U4") (pin "2") (pinfunction "MICN_2") (pintype "input+no_connect"))
    )
    (net (code "70") (name "unconnected-(U4-MICP-Pad1)") (class "Default")
      (node (ref "U4") (pin "1") (pinfunction "MICP_1") (pintype "input+no_connect"))
    )
    (net (code "71") (name "unconnected-(U4-PCM_CLK-Pad59)") (class "Default")
      (node (ref "U4") (pin "59") (pinfunction "PCM_CLK_59") (pintype "output+no_connect"))
    )
    (net (code "72") (name "unconnected-(U4-PCM_IN-Pad62)") (class "Default")
      (node (ref "U4") (pin "62") (pinfunction "PCM_IN_62") (pintype "input+no_connect"))
    )
    (net (code "73") (name "unconnected-(U4-PCM_OUT-Pad60)") (class "Default")
      (node (ref "U4") (pin "60") (pinfunction "PCM_OUT_60") (pintype "output+no_connect"))
    )
    (net (code "74") (name "unconnected-(U4-PCM_SYNC-Pad61)") (class "Default")
      (node (ref "U4") (pin "61") (pinfunction "PCM_SYNC_61") (pintype "output+no_connect"))
    )
    (net (code "75") (name "unconnected-(U4-RESERVED-Pad46)") (class "Default")
      (node (ref "U4") (pin "46") (pinfunction "RESERVED_46") (pintype "bidirectional"))
    )
    (net (code "76") (name "unconnected-(U4-RESERVED-Pad55)") (class "Default")
      (node (ref "U4") (pin "55") (pinfunction "RESERVED_55") (pintype "bidirectional"))
    )
    (net (code "77") (name "unconnected-(U4-RESERVED-Pad56)") (class "Default")
      (node (ref "U4") (pin "56") (pinfunction "RESERVED_56") (pintype "bidirectional"))
    )
    (net (code "78") (name "unconnected-(U4-RESERVED-Pad57)") (class "Default")
      (node (ref "U4") (pin "57") (pinfunction "RESERVED_57") (pintype "bidirectional"))
    )
    (net (code "79") (name "unconnected-(U4-RESERVED-Pad58)") (class "Default")
      (node (ref "U4") (pin "58") (pinfunction "RESERVED_58") (pintype "bidirectional"))
    )
    (net (code "80") (name "unconnected-(U4-RESERVED-Pad63)") (class "Default")
      (node (ref "U4") (pin "63") (pinfunction "RESERVED_63") (pintype "bidirectional"))
    )
    (net (code "81") (name "unconnected-(U4-RESERVED-Pad64)") (class "Default")
      (node (ref "U4") (pin "64") (pinfunction "RESERVED_64") (pintype "bidirectional"))
    )
    (net (code "82") (name "unconnected-(U4-RESERVED-Pad65)") (class "Default")
      (node (ref "U4") (pin "65") (pinfunction "RESERVED_65") (pintype "bidirectional"))
    )
    (net (code "83") (name "unconnected-(U4-RESERVED-Pad66)") (class "Default")
      (node (ref "U4") (pin "66") (pinfunction "RESERVED_66") (pintype "bidirectional"))
    )
    (net (code "84") (name "unconnected-(U4-RESERVED-Pad67)") (class "Default")
      (node (ref "U4") (pin "67") (pinfunction "RESERVED_67") (pintype "bidirectional"))
    )
    (net (code "85") (name "unconnected-(U4-RESERVED-Pad68)") (class "Default")
      (node (ref "U4") (pin "68") (pinfunction "RESERVED_68") (pintype "bidirectional"))
    )
    (net (code "86") (name "unconnected-(U4-RI-Pad35)") (class "Default")
      (node (ref "U4") (pin "35") (pinfunction "RI_35") (pintype "output+no_connect"))
    )
    (net (code "87") (name "unconnected-(U4-RTS-Pad39)") (class "Default")
      (node (ref "U4") (pin "39") (pinfunction "RTS_39") (pintype "input+no_connect"))
    )
    (net (code "88") (name "unconnected-(U4-SD_CLK-Pad8)") (class "Default")
      (node (ref "U4") (pin "8") (pinfunction "SD_CLK_8") (pintype "output+no_connect"))
    )
    (net (code "89") (name "unconnected-(U4-SD_CMD-Pad7)") (class "Default")
      (node (ref "U4") (pin "7") (pinfunction "SD_CMD_7") (pintype "output+no_connect"))
    )
    (net (code "90") (name "unconnected-(U4-SD_DATA-Pad9)") (class "Default")
      (node (ref "U4") (pin "9") (pinfunction "SD_DATA_9") (pintype "bidirectional+no_connect"))
    )
    (net (code "91") (name "unconnected-(U4-SIM2_CLK-Pad10)") (class "Default")
      (node (ref "U4") (pin "10") (pinfunction "SIM2_CLK_10") (pintype "output+no_connect"))
    )
    (net (code "92") (name "unconnected-(U4-SIM2_DATA-Pad11)") (class "Default")
      (node (ref "U4") (pin "11") (pinfunction "SIM2_DATA_11") (pintype "bidirectional+no_connect"))
    )
    (net (code "93") (name "unconnected-(U4-SIM2_RST-Pad12)") (class "Default")
      (node (ref "U4") (pin "12") (pinfunction "SIM2_RST_12") (pintype "output+no_connect"))
    )
    (net (code "94") (name "unconnected-(U4-SIM2_VDD-Pad13)") (class "Default")
      (node (ref "U4") (pin "13") (pinfunction "SIM2_VDD_13") (pintype "power_in+no_connect"))
    )
    (net (code "95") (name "unconnected-(U4-SPKN-Pad4)") (class "Default")
      (node (ref "U4") (pin "4") (pinfunction "SPKN_4") (pintype "output+no_connect"))
    )
    (net (code "96") (name "unconnected-(U4-SPKP-Pad3)") (class "Default")
      (node (ref "U4") (pin "3") (pinfunction "SPKP_3") (pintype "output+no_connect"))
    )
    (net (code "97") (name "unconnected-(U5-IO1-Pad39)") (class "Default")
      (node (ref "U5") (pin "39") (pinfunction "IO1_39") (pintype "bidirectional"))
    )
    (net (code "98") (name "unconnected-(U5-IO2-Pad38)") (class "Default")
      (node (ref "U5") (pin "38") (pinfunction "IO2_38") (pintype "bidirectional"))
    )
    (net (code "99") (name "unconnected-(U5-IO4-Pad4)") (class "Default")
      (node (ref "U5") (pin "4") (pinfunction "IO4_4") (pintype "bidirectional"))
    )
    (net (code "100") (name "unconnected-(U5-IO5-Pad5)") (class "Default")
      (node (ref "U5") (pin "5") (pinfunction "IO5_5") (pintype "bidirectional"))
    )
    (net (code "101") (name "unconnected-(U5-IO35-Pad28)") (class "Default")
      (node (ref "U5") (pin "28") (pinfunction "IO35_28") (pintype "bidirectional+no_connect"))
    )
    (net (code "102") (name "unconnected-(U5-IO36-Pad29)") (class "Default")
      (node (ref "U5") (pin "29") (pinfunction "IO36_29") (pintype "bidirectional+no_connect"))
    )
    (net (code "103") (name "unconnected-(U5-IO37-Pad30)") (class "Default")
      (node (ref "U5") (pin "30") (pinfunction "IO37_30") (pintype "bidirectional+no_connect"))
    )
    (net (code "104") (name "unconnected-(U5-IO47-Pad24)") (class "Default")
      (node (ref "U5") (pin "24") (pinfunction "IO47_24") (pintype "bidirectional"))
    )
    (net (code "105") (name "unconnected-(U5-IO48-Pad25)") (class "Default")
      (node (ref "U5") (pin "25") (pinfunction "IO48_25") (pintype "bidirectional"))
    )
  )
)
